# Autonomy.net
KiCad netlist of a schematic drawn in EAGLE
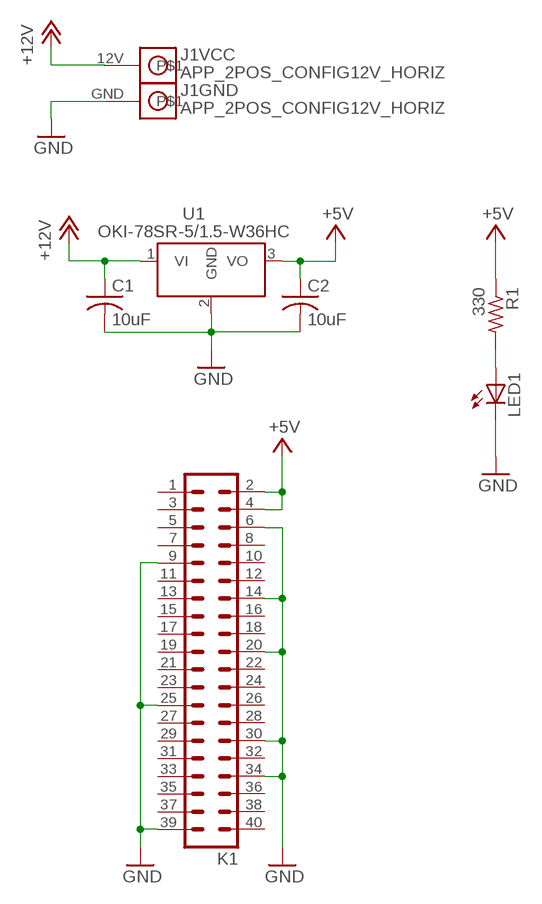
[diagram p0: schematic, sheet 1]

(export (version "E")
  (design (tool "Eeschema 10.0.6"))
  (components
    (comp (ref "C1")
      (value "10uF")
      (footprint "eagle-import:C1206")
      (libsource (lib "eagle-import") (part "C-USC1206"))
    )
    (comp (ref "C2")
      (value "10uF")
      (footprint "eagle-import:C1206")
      (libsource (lib "eagle-import") (part "C-USC1206"))
    )
    (comp (ref "J1")
      (value "APP_2POS_CONFIG12V_HORIZ")
      (footprint "eagle-import:APP45_12V_HORIZ_CONFIG")
      (libsource (lib "eagle-import") (part "APP_2POS_CONFIG12V_HORIZ"))
    )
    (comp (ref "K1")
      (value "MA20-2")
      (footprint "eagle-import:MA20-2")
      (libsource (lib "eagle-import") (part "MA20-2"))
    )
    (comp (ref "LED1")
      (value "LEDCHIPLED_1206")
      (footprint "eagle-import:CHIPLED_1206")
      (libsource (lib "eagle-import") (part "LEDCHIPLED_1206"))
    )
    (comp (ref "R1")
      (value "330")
      (footprint "eagle-import:R1206")
      (libsource (lib "eagle-import") (part "R-US_R1206"))
    )
    (comp (ref "U1")
      (value "OKI-78SR-5/1.5-W36HC")
      (footprint "eagle-import:OKI-78SR_HORIZ")
      (libsource (lib "eagle-import") (part "OKI-78SR-/1.5-W36?CH5"))
    )
  )
  (nets
    (net (code "1") (name "+5V") (class "Default")
      (node (ref "C2") (pin "1") (pinfunction "1_1") (pintype "passive"))
      (node (ref "K1") (pin "2") (pinfunction "2_2") (pintype "passive"))
      (node (ref "K1") (pin "4") (pinfunction "4_4") (pintype "passive"))
      (node (ref "R1") (pin "1") (pinfunction "1_1") (pintype "passive"))
      (node (ref "U1") (pin "3") (pinfunction "VO_3") (pintype "bidirectional"))
    )
    (net (code "2") (name "+12V") (class "Default")
      (node (ref "C1") (pin "1") (pinfunction "1_1") (pintype "passive"))
      (node (ref "J1") (pin "12V") (pinfunction "P$1_12V") (pintype "bidirectional"))
      (node (ref "U1") (pin "1") (pinfunction "VI_1") (pintype "bidirectional"))
    )
    (net (code "3") (name "GND") (class "Default")
      (node (ref "C1") (pin "2") (pinfunction "2_2") (pintype "passive"))
      (node (ref "C2") (pin "2") (pinfunction "2_2") (pintype "passive"))
      (node (ref "J1") (pin "GND") (pinfunction "P$1_GND") (pintype "bidirectional"))
      (node (ref "K1") (pin "14") (pinfunction "14_14") (pintype "passive"))
      (node (ref "K1") (pin "20") (pinfunction "20_20") (pintype "passive"))
      (node (ref "K1") (pin "25") (pinfunction "25_25") (pintype "passive"))
      (node (ref "K1") (pin "30") (pinfunction "30_30") (pintype "passive"))
      (node (ref "K1") (pin "34") (pinfunction "34_34") (pintype "passive"))
      (node (ref "K1") (pin "39") (pinfunction "39_39") (pintype "passive"))
      (node (ref "K1") (pin "6") (pinfunction "6_6") (pintype "passive"))
      (node (ref "K1") (pin "9") (pinfunction "9_9") (pintype "passive"))
      (node (ref "LED1") (pin "C") (pinfunction "C_C") (pintype "passive"))
      (node (ref "U1") (pin "2") (pinfunction "GND_2") (pintype "bidirectional"))
    )
    (net (code "4") (name "Net-(LED1-PadA)") (class "Default")
      (node (ref "LED1") (pin "A") (pinfunction "A_A") (pintype "passive"))
      (node (ref "R1") (pin "2") (pinfunction "2_2") (pintype "passive"))
    )
    (net (code "5") (name "unconnected-(K1-Pad1)") (class "Default")
      (node (ref "K1") (pin "1") (pinfunction "1_1") (pintype "passive"))
    )
    (net (code "6") (name "unconnected-(K1-Pad3)") (class "Default")
      (node (ref "K1") (pin "3") (pinfunction "3_3") (pintype "passive"))
    )
    (net (code "7") (name "unconnected-(K1-Pad5)") (class "Default")
      (node (ref "K1") (pin "5") (pinfunction "5_5") (pintype "passive"))
    )
    (net (code "8") (name "unconnected-(K1-Pad7)") (class "Default")
      (node (ref "K1") (pin "7") (pinfunction "7_7") (pintype "passive"))
    )
    (net (code "9") (name "unconnected-(K1-Pad8)") (class "Default")
      (node (ref "K1") (pin "8") (pinfunction "8_8") (pintype "passive"))
    )
    (net (code "10") (name "unconnected-(K1-Pad10)") (class "Default")
      (node (ref "K1") (pin "10") (pinfunction "10_10") (pintype "passive"))
    )
    (net (code "11") (name "unconnected-(K1-Pad11)") (class "Default")
      (node (ref "K1") (pin "11") (pinfunction "11_11") (pintype "passive"))
    )
    (net (code "12") (name "unconnected-(K1-Pad12)") (class "Default")
      (node (ref "K1") (pin "12") (pinfunction "12_12") (pintype "passive"))
    )
    (net (code "13") (name "unconnected-(K1-Pad13)") (class "Default")
      (node (ref "K1") (pin "13") (pinfunction "13_13") (pintype "passive"))
    )
    (net (code "14") (name "unconnected-(K1-Pad15)") (class "Default")
      (node (ref "K1") (pin "15") (pinfunction "15_15") (pintype "passive"))
    )
    (net (code "15") (name "unconnected-(K1-Pad16)") (class "Default")
      (node (ref "K1") (pin "16") (pinfunction "16_16") (pintype "passive"))
    )
    (net (code "16") (name "unconnected-(K1-Pad17)") (class "Default")
      (node (ref "K1") (pin "17") (pinfunction "17_17") (pintype "passive"))
    )
    (net (code "17") (name "unconnected-(K1-Pad18)") (class "Default")
      (node (ref "K1") (pin "18") (pinfunction "18_18") (pintype "passive"))
    )
    (net (code "18") (name "unconnected-(K1-Pad19)") (class "Default")
      (node (ref "K1") (pin "19") (pinfunction "19_19") (pintype "passive"))
    )
    (net (code "19") (name "unconnected-(K1-Pad21)") (class "Default")
      (node (ref "K1") (pin "21") (pinfunction "21_21") (pintype "passive"))
    )
    (net (code "20") (name "unconnected-(K1-Pad22)") (class "Default")
      (node (ref "K1") (pin "22") (pinfunction "22_22") (pintype "passive"))
    )
    (net (code "21") (name "unconnected-(K1-Pad23)") (class "Default")
      (node (ref "K1") (pin "23") (pinfunction "23_23") (pintype "passive"))
    )
    (net (code "22") (name "unconnected-(K1-Pad24)") (class "Default")
      (node (ref "K1") (pin "24") (pinfunction "24_24") (pintype "passive"))
    )
    (net (code "23") (name "unconnected-(K1-Pad26)") (class "Default")
      (node (ref "K1") (pin "26") (pinfunction "26_26") (pintype "passive"))
    )
    (net (code "24") (name "unconnected-(K1-Pad27)") (class "Default")
      (node (ref "K1") (pin "27") (pinfunction "27_27") (pintype "passive"))
    )
    (net (code "25") (name "unconnected-(K1-Pad28)") (class "Default")
      (node (ref "K1") (pin "28") (pinfunction "28_28") (pintype "passive"))
    )
    (net (code "26") (name "unconnected-(K1-Pad29)") (class "Default")
      (node (ref "K1") (pin "29") (pinfunction "29_29") (pintype "passive"))
    )
    (net (code "27") (name "unconnected-(K1-Pad31)") (class "Default")
      (node (ref "K1") (pin "31") (pinfunction "31_31") (pintype "passive"))
    )
    (net (code "28") (name "unconnected-(K1-Pad32)") (class "Default")
      (node (ref "K1") (pin "32") (pinfunction "32_32") (pintype "passive"))
    )
    (net (code "29") (name "unconnected-(K1-Pad33)") (class "Default")
      (node (ref "K1") (pin "33") (pinfunction "33_33") (pintype "passive"))
    )
    (net (code "30") (name "unconnected-(K1-Pad35)") (class "Default")
      (node (ref "K1") (pin "35") (pinfunction "35_35") (pintype "passive"))
    )
    (net (code "31") (name "unconnected-(K1-Pad36)") (class "Default")
      (node (ref "K1") (pin "36") (pinfunction "36_36") (pintype "passive"))
    )
    (net (code "32") (name "unconnected-(K1-Pad37)") (class "Default")
      (node (ref "K1") (pin "37") (pinfunction "37_37") (pintype "passive"))
    )
    (net (code "33") (name "unconnected-(K1-Pad38)") (class "Default")
      (node (ref "K1") (pin "38") (pinfunction "38_38") (pintype "passive"))
    )
    (net (code "34") (name "unconnected-(K1-Pad40)") (class "Default")
      (node (ref "K1") (pin "40") (pinfunction "40_40") (pintype "passive"))
    )
  )
)
